# Delay_Circuit.net
KiCad netlist of a schematic drawn in EAGLE
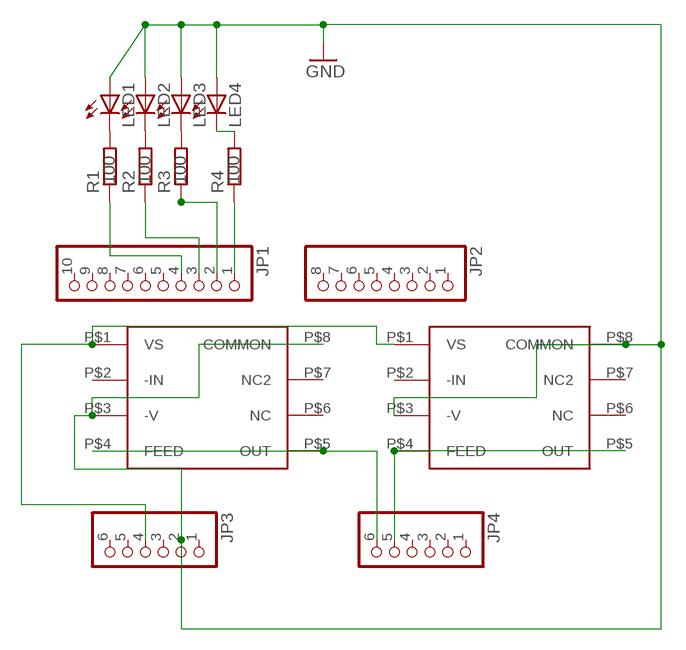
[diagram p0: schematic, sheet 1]

(export (version "E")
  (design (tool "Eeschema 10.0.6"))
  (components
    (comp (ref "JP1")
      (value "PINHD-1X10")
      (footprint "eagle-import:1X10")
      (libsource (lib "eagle-import") (part "PINHD-1X10"))
    )
    (comp (ref "JP2")
      (value "PINHD-1X8")
      (footprint "eagle-import:1X08")
      (libsource (lib "eagle-import") (part "PINHD-1X8"))
    )
    (comp (ref "JP3")
      (value "PINHD-1X6")
      (footprint "eagle-import:1X06")
      (libsource (lib "eagle-import") (part "PINHD-1X6"))
    )
    (comp (ref "JP4")
      (value "PINHD-1X6")
      (footprint "eagle-import:1X06")
      (libsource (lib "eagle-import") (part "PINHD-1X6"))
    )
    (comp (ref "LED1")
      (value "LED5MM")
      (footprint "eagle-import:LED5MM")
      (libsource (lib "eagle-import") (part "LED5MM"))
    )
    (comp (ref "LED2")
      (value "LED5MM")
      (footprint "eagle-import:LED5MM")
      (libsource (lib "eagle-import") (part "LED5MM"))
    )
    (comp (ref "LED3")
      (value "LED5MM")
      (footprint "eagle-import:LED5MM")
      (libsource (lib "eagle-import") (part "LED5MM"))
    )
    (comp (ref "LED4")
      (value "LED5MM")
      (footprint "eagle-import:LED5MM")
      (libsource (lib "eagle-import") (part "LED5MM"))
    )
    (comp (ref "OPT101_1")
      (value "OPT101P")
      (footprint "eagle-import:OPT101P")
      (libsource (lib "eagle-import") (part "OPT101P"))
    )
    (comp (ref "OPT101_2")
      (value "OPT101P")
      (footprint "eagle-import:OPT101P")
      (libsource (lib "eagle-import") (part "OPT101P"))
    )
    (comp (ref "R1")
      (value "100")
      (footprint "eagle-import:0204_7")
      (libsource (lib "eagle-import") (part "R0204/7"))
    )
    (comp (ref "R2")
      (value "100")
      (footprint "eagle-import:0204_7")
      (libsource (lib "eagle-import") (part "R0204/7"))
    )
    (comp (ref "R3")
      (value "100")
      (footprint "eagle-import:0204_7")
      (libsource (lib "eagle-import") (part "R0204/7"))
    )
    (comp (ref "R4")
      (value "100")
      (footprint "eagle-import:0204_7")
      (libsource (lib "eagle-import") (part "R0204/7"))
    )
  )
  (nets
    (net (code "1") (name "GND") (class "Default")
      (node (ref "JP3") (pin "2") (pinfunction "2_2") (pintype "passive"))
      (node (ref "LED1") (pin "A") (pinfunction "A_A") (pintype "passive"))
      (node (ref "LED2") (pin "A") (pinfunction "A_A") (pintype "passive"))
      (node (ref "LED3") (pin "A") (pinfunction "A_A") (pintype "passive"))
      (node (ref "LED4") (pin "A") (pinfunction "A_A") (pintype "passive"))
      (node (ref "OPT101_1") (pin "P$3") (pinfunction "-V_P$3") (pintype "bidirectional"))
      (node (ref "OPT101_1") (pin "P$8") (pinfunction "COMMON_P$8") (pintype "bidirectional"))
      (node (ref "OPT101_2") (pin "P$3") (pinfunction "-V_P$3") (pintype "bidirectional"))
      (node (ref "OPT101_2") (pin "P$8") (pinfunction "COMMON_P$8") (pintype "bidirectional"))
    )
    (net (code "2") (name "Net-(JP1-Pad1)") (class "Default")
      (node (ref "JP1") (pin "1") (pinfunction "1_1") (pintype "passive"))
      (node (ref "R4") (pin "1") (pinfunction "1_1") (pintype "passive"))
    )
    (net (code "3") (name "Net-(JP1-Pad2)") (class "Default")
      (node (ref "JP1") (pin "2") (pinfunction "2_2") (pintype "passive"))
      (node (ref "R3") (pin "1") (pinfunction "1_1") (pintype "passive"))
    )
    (net (code "4") (name "Net-(JP1-Pad3)") (class "Default")
      (node (ref "JP1") (pin "3") (pinfunction "3_3") (pintype "passive"))
      (node (ref "R2") (pin "1") (pinfunction "1_1") (pintype "passive"))
    )
    (net (code "5") (name "Net-(JP1-Pad4)") (class "Default")
      (node (ref "JP1") (pin "4") (pinfunction "4_4") (pintype "passive"))
      (node (ref "R1") (pin "1") (pinfunction "1_1") (pintype "passive"))
    )
    (net (code "6") (name "Net-(LED1-C)") (class "Default")
      (node (ref "LED1") (pin "K") (pinfunction "C_K") (pintype "passive"))
      (node (ref "R1") (pin "2") (pinfunction "2_2") (pintype "passive"))
    )
    (net (code "7") (name "Net-(LED2-C)") (class "Default")
      (node (ref "LED2") (pin "K") (pinfunction "C_K") (pintype "passive"))
      (node (ref "R2") (pin "2") (pinfunction "2_2") (pintype "passive"))
    )
    (net (code "8") (name "Net-(LED3-C)") (class "Default")
      (node (ref "LED3") (pin "K") (pinfunction "C_K") (pintype "passive"))
      (node (ref "R3") (pin "2") (pinfunction "2_2") (pintype "passive"))
    )
    (net (code "9") (name "Net-(LED4-C)") (class "Default")
      (node (ref "LED4") (pin "K") (pinfunction "C_K") (pintype "passive"))
      (node (ref "R4") (pin "2") (pinfunction "2_2") (pintype "passive"))
    )
    (net (code "10") (name "Net-(OPT101_1-FEED)") (class "Default")
      (node (ref "JP4") (pin "6") (pinfunction "6_6") (pintype "passive"))
      (node (ref "OPT101_1") (pin "P$4") (pinfunction "FEED_P$4") (pintype "bidirectional"))
      (node (ref "OPT101_1") (pin "P$5") (pinfunction "OUT_P$5") (pintype "bidirectional"))
    )
    (net (code "11") (name "Net-(OPT101_1-VS)") (class "Default")
      (node (ref "JP3") (pin "4") (pinfunction "4_4") (pintype "passive"))
      (node (ref "OPT101_1") (pin "P$1") (pinfunction "VS_P$1") (pintype "bidirectional"))
      (node (ref "OPT101_2") (pin "P$1") (pinfunction "VS_P$1") (pintype "bidirectional"))
    )
    (net (code "12") (name "Net-(OPT101_2-FEED)") (class "Default")
      (node (ref "JP4") (pin "5") (pinfunction "5_5") (pintype "passive"))
      (node (ref "OPT101_2") (pin "P$4") (pinfunction "FEED_P$4") (pintype "bidirectional"))
      (node (ref "OPT101_2") (pin "P$5") (pinfunction "OUT_P$5") (pintype "bidirectional"))
    )
    (net (code "13") (name "unconnected-(JP1-Pad5)") (class "Default")
      (node (ref "JP1") (pin "5") (pinfunction "5_5") (pintype "passive"))
    )
    (net (code "14") (name "unconnected-(JP1-Pad6)") (class "Default")
      (node (ref "JP1") (pin "6") (pinfunction "6_6") (pintype "passive"))
    )
    (net (code "15") (name "unconnected-(JP1-Pad7)") (class "Default")
      (node (ref "JP1") (pin "7") (pinfunction "7_7") (pintype "passive"))
    )
    (net (code "16") (name "unconnected-(JP1-Pad8)") (class "Default")
      (node (ref "JP1") (pin "8") (pinfunction "8_8") (pintype "passive"))
    )
    (net (code "17") (name "unconnected-(JP1-Pad9)") (class "Default")
      (node (ref "JP1") (pin "9") (pinfunction "9_9") (pintype "passive"))
    )
    (net (code "18") (name "unconnected-(JP1-Pad10)") (class "Default")
      (node (ref "JP1") (pin "10") (pinfunction "10_10") (pintype "passive"))
    )
    (net (code "19") (name "unconnected-(JP2-Pad1)") (class "Default")
      (node (ref "JP2") (pin "1") (pinfunction "1_1") (pintype "passive"))
    )
    (net (code "20") (name "unconnected-(JP2-Pad2)") (class "Default")
      (node (ref "JP2") (pin "2") (pinfunction "2_2") (pintype "passive"))
    )
    (net (code "21") (name "unconnected-(JP2-Pad3)") (class "Default")
      (node (ref "JP2") (pin "3") (pinfunction "3_3") (pintype "passive"))
    )
    (net (code "22") (name "unconnected-(JP2-Pad4)") (class "Default")
      (node (ref "JP2") (pin "4") (pinfunction "4_4") (pintype "passive"))
    )
    (net (code "23") (name "unconnected-(JP2-Pad5)") (class "Default")
      (node (ref "JP2") (pin "5") (pinfunction "5_5") (pintype "passive"))
    )
    (net (code "24") (name "unconnected-(JP2-Pad6)") (class "Default")
      (node (ref "JP2") (pin "6") (pinfunction "6_6") (pintype "passive"))
    )
    (net (code "25") (name "unconnected-(JP2-Pad7)") (class "Default")
      (node (ref "JP2") (pin "7") (pinfunction "7_7") (pintype "passive"))
    )
    (net (code "26") (name "unconnected-(JP2-Pad8)") (class "Default")
      (node (ref "JP2") (pin "8") (pinfunction "8_8") (pintype "passive"))
    )
    (net (code "27") (name "unconnected-(JP3-Pad1)") (class "Default")
      (node (ref "JP3") (pin "1") (pinfunction "1_1") (pintype "passive"))
    )
    (net (code "28") (name "unconnected-(JP3-Pad3)") (class "Default")
      (node (ref "JP3") (pin "3") (pinfunction "3_3") (pintype "passive"))
    )
    (net (code "29") (name "unconnected-(JP3-Pad5)") (class "Default")
      (node (ref "JP3") (pin "5") (pinfunction "5_5") (pintype "passive"))
    )
    (net (code "30") (name "unconnected-(JP3-Pad6)") (class "Default")
      (node (ref "JP3") (pin "6") (pinfunction "6_6") (pintype "passive"))
    )
    (net (code "31") (name "unconnected-(JP4-Pad1)") (class "Default")
      (node (ref "JP4") (pin "1") (pinfunction "1_1") (pintype "passive"))
    )
    (net (code "32") (name "unconnected-(JP4-Pad2)") (class "Default")
      (node (ref "JP4") (pin "2") (pinfunction "2_2") (pintype "passive"))
    )
    (net (code "33") (name "unconnected-(JP4-Pad3)") (class "Default")
      (node (ref "JP4") (pin "3") (pinfunction "3_3") (pintype "passive"))
    )
    (net (code "34") (name "unconnected-(JP4-Pad4)") (class "Default")
      (node (ref "JP4") (pin "4") (pinfunction "4_4") (pintype "passive"))
    )
    (net (code "35") (name "unconnected-(OPT101_1--IN-PadP$2)") (class "Default")
      (node (ref "OPT101_1") (pin "P$2") (pinfunction "-IN_P$2") (pintype "bidirectional"))
    )
    (net (code "36") (name "unconnected-(OPT101_1-NC-PadP$6)") (class "Default")
      (node (ref "OPT101_1") (pin "P$6") (pinfunction "NC_P$6") (pintype "bidirectional"))
    )
    (net (code "37") (name "unconnected-(OPT101_1-NC2-PadP$7)") (class "Default")
      (node (ref "OPT101_1") (pin "P$7") (pinfunction "NC2_P$7") (pintype "bidirectional"))
    )
    (net (code "38") (name "unconnected-(OPT101_2--IN-PadP$2)") (class "Default")
      (node (ref "OPT101_2") (pin "P$2") (pinfunction "-IN_P$2") (pintype "bidirectional"))
    )
    (net (code "39") (name "unconnected-(OPT101_2-NC-PadP$6)") (class "Default")
      (node (ref "OPT101_2") (pin "P$6") (pinfunction "NC_P$6") (pintype "bidirectional"))
    )
    (net (code "40") (name "unconnected-(OPT101_2-NC2-PadP$7)") (class "Default")
      (node (ref "OPT101_2") (pin "P$7") (pinfunction "NC2_P$7") (pintype "bidirectional"))
    )
  )
)
